# LPCB224_-_CAN.net
KiCad netlist of a schematic drawn in Altium Designer
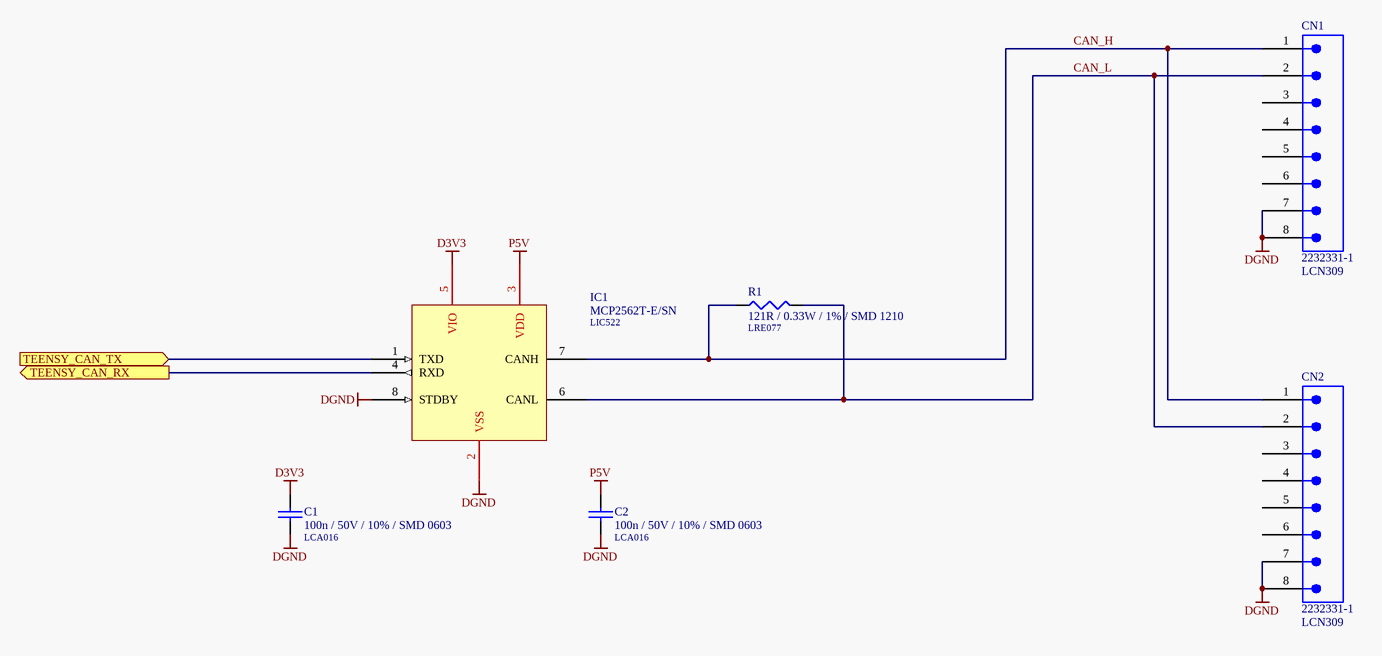
[diagram p0: LPCB224 - CAN.SchDoc]

(export (version "E")
  (design (tool "Eeschema 10.0.6"))
  (components
    (comp (ref "C1")
      (value "100n / 50V / 10% / SMD 0603")
      (footprint "LFP011__CC1608-0603-IPC7351_B")
      (description "Capacitor, Ceramic Chip, 100nF (0.1uF), 50V, 5%, SMD 0603 [LCA016]")
      (fields (field (name "LDL_NUMBER") "LCA016"))
      (libsource (lib "LDL_Capacitors") (part "100n / 50V / 10% / SMD 0603"))
    )
    (comp (ref "C2")
      (value "100n / 50V / 10% / SMD 0603")
      (footprint "LFP011__CC1608-0603-IPC7351_B")
      (description "Capacitor, Ceramic Chip, 100nF (0.1uF), 50V, 5%, SMD 0603 [LCA016]")
      (fields (field (name "LDL_NUMBER") "LCA016"))
      (libsource (lib "LDL_Capacitors") (part "100n / 50V / 10% / SMD 0603"))
    )
    (comp (ref "CN1")
      (value "2232331-1")
      (footprint "2232331-1")
      (description "Connector, M12 8 Way, PCB Mount")
      (fields (field (name "LDL_NUMBER") "LCN309"))
      (libsource (lib "LDL_Connectors") (part "2232331-1"))
    )
    (comp (ref "CN2")
      (value "2232331-1")
      (footprint "2232331-1")
      (description "Connector, M12 8 Way, PCB Mount")
      (fields (field (name "LDL_NUMBER") "LCN309"))
      (libsource (lib "LDL_Connectors") (part "2232331-1"))
    )
    (comp (ref "IC1")
      (value "MCP2562T-E/SN")
      (footprint "LFP017__SO-G8/Y1.9")
      (description "IC, High Speed CAN Transceiver, SMD SOIC8 [LIC522]")
      (fields (field (name "LDL_NUMBER") "LIC522"))
      (libsource (lib "LDL_Semiconductors") (part "MCP2562T-E/SN"))
    )
    (comp (ref "R1")
      (value "121R / 0.33W / 1% / SMD 1210")
      (footprint "LFP028__CR3225-1210")
      (description "Resistor, Ceramic Chip, 121R, 0.33W, 1%, SMD 1210 [LRE077]")
      (fields (field (name "LDL_NUMBER") "LRE077"))
      (libsource (lib "LDL_Resistors") (part "121R / 0.33W / 1% / SMD 1210"))
    )
  )
  (nets
    (net (code "1") (name "/CAN_H") (class "Default")
      (node (ref "CN1") (pin "1") (pinfunction "1_1") (pintype "passive"))
      (node (ref "CN2") (pin "1") (pinfunction "1_1") (pintype "passive"))
      (node (ref "IC1") (pin "7") (pinfunction "CANH_7") (pintype "passive"))
      (node (ref "R1") (pin "1") (pintype "passive"))
    )
    (net (code "2") (name "/CAN_L") (class "Default")
      (node (ref "CN1") (pin "2") (pinfunction "2_2") (pintype "passive"))
      (node (ref "CN2") (pin "2") (pinfunction "2_2") (pintype "passive"))
      (node (ref "IC1") (pin "6") (pinfunction "CANL_6") (pintype "passive"))
      (node (ref "R1") (pin "2") (pintype "passive"))
    )
    (net (code "3") (name "/TEENSY_CAN_RX") (class "Default")
      (node (ref "IC1") (pin "4") (pinfunction "RXD_4") (pintype "output"))
    )
    (net (code "4") (name "/TEENSY_CAN_TX") (class "Default")
      (node (ref "IC1") (pin "1") (pinfunction "TXD_1") (pintype "input"))
    )
    (net (code "5") (name "D3V3") (class "Default")
      (node (ref "C1") (pin "1") (pintype "passive"))
      (node (ref "IC1") (pin "5") (pinfunction "VIO_5") (pintype "power_in"))
    )
    (net (code "6") (name "DGND") (class "Default")
      (node (ref "C1") (pin "2") (pintype "passive"))
      (node (ref "C2") (pin "2") (pintype "passive"))
      (node (ref "CN1") (pin "7") (pinfunction "7_7") (pintype "passive"))
      (node (ref "CN1") (pin "8") (pinfunction "8_8") (pintype "passive"))
      (node (ref "CN2") (pin "7") (pinfunction "7_7") (pintype "passive"))
      (node (ref "CN2") (pin "8") (pinfunction "8_8") (pintype "passive"))
      (node (ref "IC1") (pin "2") (pinfunction "VSS_2") (pintype "passive"))
      (node (ref "IC1") (pin "8") (pinfunction "STDBY_8") (pintype "input"))
    )
    (net (code "7") (name "P5V") (class "Default")
      (node (ref "C2") (pin "1") (pintype "passive"))
      (node (ref "IC1") (pin "3") (pinfunction "VDD_3") (pintype "passive"))
    )
    (net (code "8") (name "unconnected-(CN1-Pad3)") (class "Default")
      (node (ref "CN1") (pin "3") (pinfunction "3_3") (pintype "passive"))
    )
    (net (code "9") (name "unconnected-(CN1-Pad4)") (class "Default")
      (node (ref "CN1") (pin "4") (pinfunction "4_4") (pintype "passive"))
    )
    (net (code "10") (name "unconnected-(CN1-Pad5)") (class "Default")
      (node (ref "CN1") (pin "5") (pinfunction "5_5") (pintype "passive"))
    )
    (net (code "11") (name "unconnected-(CN1-Pad6)") (class "Default")
      (node (ref "CN1") (pin "6") (pinfunction "6_6") (pintype "passive"))
    )
    (net (code "12") (name "unconnected-(CN2-Pad3)") (class "Default")
      (node (ref "CN2") (pin "3") (pinfunction "3_3") (pintype "passive"))
    )
    (net (code "13") (name "unconnected-(CN2-Pad4)") (class "Default")
      (node (ref "CN2") (pin "4") (pinfunction "4_4") (pintype "passive"))
    )
    (net (code "14") (name "unconnected-(CN2-Pad5)") (class "Default")
      (node (ref "CN2") (pin "5") (pinfunction "5_5") (pintype "passive"))
    )
    (net (code "15") (name "unconnected-(CN2-Pad6)") (class "Default")
      (node (ref "CN2") (pin "6") (pinfunction "6_6") (pintype "passive"))
    )
  )
)
